# untitled.net
KiCad netlist of a schematic drawn in EAGLE
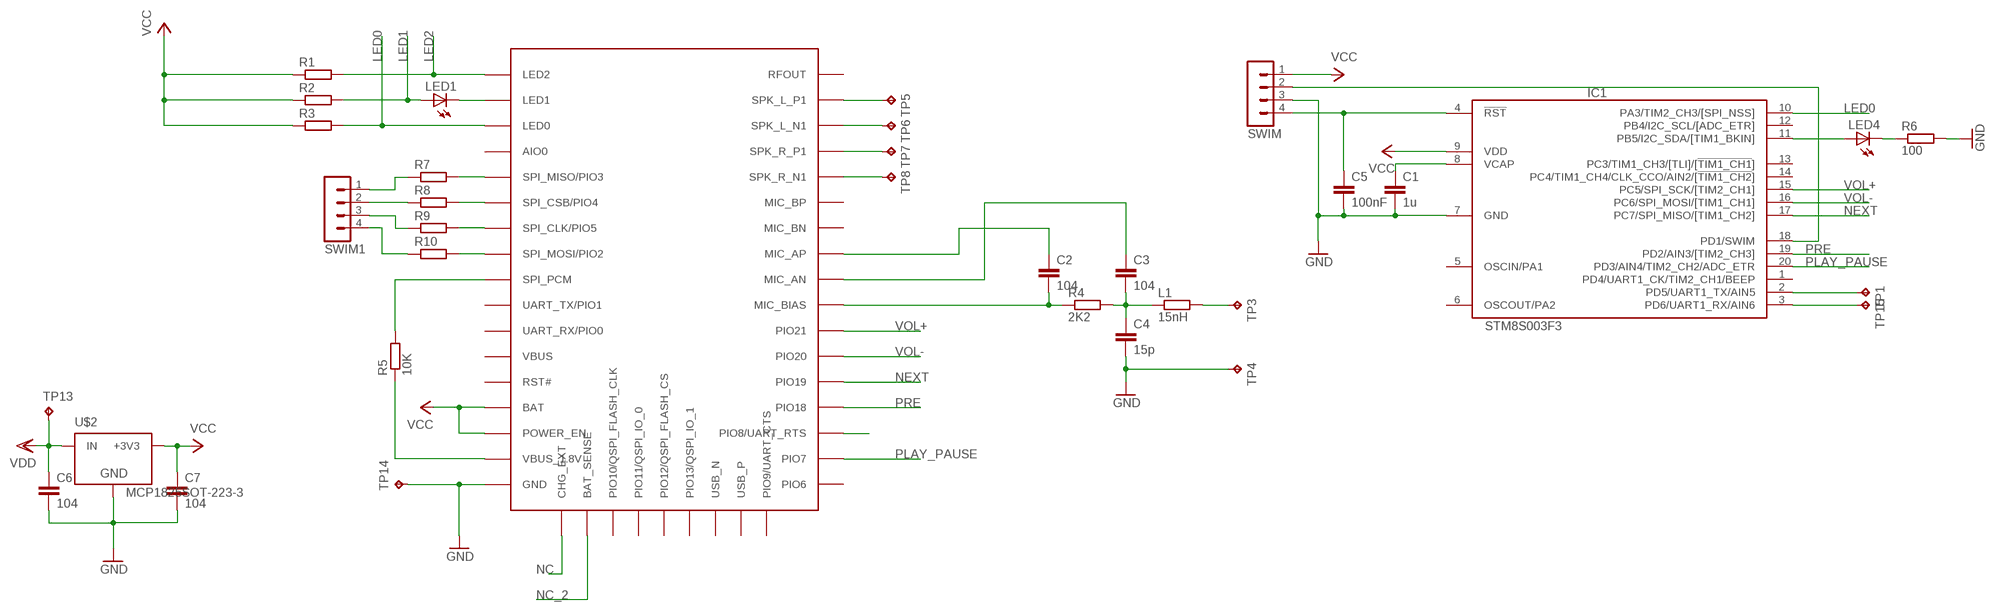
[diagram p0: schematic, sheet 1]

(export (version "E")
  (design (tool "Eeschema 10.0.6"))
  (components
    (comp (ref "C1")
      (value "1u")
      (footprint "eagle-import:C0805")
      (libsource (lib "eagle-import") (part "C-EUC0805"))
    )
    (comp (ref "C2")
      (value "104")
      (footprint "eagle-import:C0805")
      (libsource (lib "eagle-import") (part "C-EUC0805"))
    )
    (comp (ref "C3")
      (value "104")
      (footprint "eagle-import:C0805")
      (libsource (lib "eagle-import") (part "C-EUC0805"))
    )
    (comp (ref "C4")
      (value "15p")
      (footprint "eagle-import:C0805")
      (libsource (lib "eagle-import") (part "C-EUC0805"))
    )
    (comp (ref "C5")
      (value "100nF")
      (footprint "eagle-import:C0805")
      (libsource (lib "eagle-import") (part "C-EUC0805"))
    )
    (comp (ref "C6")
      (value "104")
      (footprint "eagle-import:C0805")
      (libsource (lib "eagle-import") (part "C-EUC0805"))
    )
    (comp (ref "C7")
      (value "104")
      (footprint "eagle-import:C0805")
      (libsource (lib "eagle-import") (part "C-EUC0805"))
    )
    (comp (ref "IC1")
      (value "STM8S003F3")
      (footprint "eagle-import:TSSOP20")
      (libsource (lib "eagle-import") (part "STM8S003F3"))
    )
    (comp (ref "L1")
      (value "15nH")
      (footprint "eagle-import:R0603")
      (libsource (lib "eagle-import") (part "R-EU_R0603"))
    )
    (comp (ref "LED1")
      (value "LEDCHIPLED_0603")
      (footprint "eagle-import:CHIPLED_0603")
      (libsource (lib "eagle-import") (part "LEDCHIPLED_0603"))
    )
    (comp (ref "LED4")
      (value "LEDCHIPLED_0603")
      (footprint "eagle-import:CHIPLED_0603")
      (libsource (lib "eagle-import") (part "LEDCHIPLED_0603"))
    )
    (comp (ref "R1")
      (value "R-EU_R0805")
      (footprint "eagle-import:R0805")
      (libsource (lib "eagle-import") (part "R-EU_R0805"))
    )
    (comp (ref "R2")
      (value "R-EU_R0805")
      (footprint "eagle-import:R0805")
      (libsource (lib "eagle-import") (part "R-EU_R0805"))
    )
    (comp (ref "R3")
      (value "R-EU_R0805")
      (footprint "eagle-import:R0805")
      (libsource (lib "eagle-import") (part "R-EU_R0805"))
    )
    (comp (ref "R4")
      (value "2K2")
      (footprint "eagle-import:R0805")
      (libsource (lib "eagle-import") (part "R-EU_R0805"))
    )
    (comp (ref "R5")
      (value "10K")
      (footprint "eagle-import:R0805")
      (libsource (lib "eagle-import") (part "R-EU_R0805"))
    )
    (comp (ref "R6")
      (value "100")
      (footprint "eagle-import:R0805")
      (libsource (lib "eagle-import") (part "R-EU_R0805"))
    )
    (comp (ref "R7")
      (value "R-EU_R0805")
      (footprint "eagle-import:R0805")
      (libsource (lib "eagle-import") (part "R-EU_R0805"))
    )
    (comp (ref "R8")
      (value "R-EU_R0805")
      (footprint "eagle-import:R0805")
      (libsource (lib "eagle-import") (part "R-EU_R0805"))
    )
    (comp (ref "R9")
      (value "R-EU_R0805")
      (footprint "eagle-import:R0805")
      (libsource (lib "eagle-import") (part "R-EU_R0805"))
    )
    (comp (ref "R10")
      (value "R-EU_R0805")
      (footprint "eagle-import:R0805")
      (libsource (lib "eagle-import") (part "R-EU_R0805"))
    )
    (comp (ref "SWIM")
      (value "MA04-1")
      (footprint "eagle-import:MA04-1")
      (libsource (lib "eagle-import") (part "MA04-1"))
    )
    (comp (ref "SWIM1")
      (value "MA04-1")
      (footprint "eagle-import:MA04-1")
      (libsource (lib "eagle-import") (part "MA04-1"))
    )
    (comp (ref "TP1")
      (value "TPB2,54")
      (footprint "eagle-import:B2,54")
      (libsource (lib "eagle-import") (part "TPB2,54"))
    )
    (comp (ref "TP3")
      (value "TPB2,54")
      (footprint "eagle-import:B2,54")
      (libsource (lib "eagle-import") (part "TPB2,54"))
    )
    (comp (ref "TP4")
      (value "TPB2,54")
      (footprint "eagle-import:B2,54")
      (libsource (lib "eagle-import") (part "TPB2,54"))
    )
    (comp (ref "TP5")
      (value "TPB2,54")
      (footprint "eagle-import:B2,54")
      (libsource (lib "eagle-import") (part "TPB2,54"))
    )
    (comp (ref "TP6")
      (value "TPB2,54")
      (footprint "eagle-import:B2,54")
      (libsource (lib "eagle-import") (part "TPB2,54"))
    )
    (comp (ref "TP7")
      (value "TPB2,54")
      (footprint "eagle-import:B2,54")
      (libsource (lib "eagle-import") (part "TPB2,54"))
    )
    (comp (ref "TP8")
      (value "TPB2,54")
      (footprint "eagle-import:B2,54")
      (libsource (lib "eagle-import") (part "TPB2,54"))
    )
    (comp (ref "TP13")
      (value "TPB2,54")
      (footprint "eagle-import:B2,54")
      (libsource (lib "eagle-import") (part "TPB2,54"))
    )
    (comp (ref "TP14")
      (value "TPB2,54")
      (footprint "eagle-import:B2,54")
      (libsource (lib "eagle-import") (part "TPB2,54"))
    )
    (comp (ref "TP15")
      (value "TPB2,54")
      (footprint "eagle-import:B2,54")
      (libsource (lib "eagle-import") (part "TPB2,54"))
    )
    (comp (ref "U$1")
      (value "F3188")
      (footprint "eagle-import:F3188")
      (libsource (lib "eagle-import") (part "F3188"))
    )
    (comp (ref "U$2")
      (value "MCP1825SOT-223-3")
      (footprint "eagle-import:SOT-223")
      (libsource (lib "eagle-import") (part "MCP1825SOT-223-3"))
    )
  )
  (nets
    (net (code "1") (name "/LED0") (class "Default")
      (node (ref "IC1") (pin "10") (pinfunction "PA3/TIM2_CH3/[SPI_NSS]_10") (pintype "bidirectional"))
      (node (ref "R3") (pin "2") (pinfunction "2_2") (pintype "passive"))
      (node (ref "U$1") (pin "P$3") (pinfunction "LED0_P$3") (pintype "bidirectional"))
    )
    (net (code "2") (name "/LED1") (class "Default")
      (node (ref "LED1") (pin "A") (pinfunction "A_A") (pintype "passive"))
      (node (ref "R2") (pin "2") (pinfunction "2_2") (pintype "passive"))
    )
    (net (code "3") (name "/LED2") (class "Default")
      (node (ref "R1") (pin "2") (pinfunction "2_2") (pintype "passive"))
      (node (ref "U$1") (pin "P$1") (pinfunction "LED2_P$1") (pintype "bidirectional"))
    )
    (net (code "4") (name "/NC") (class "Default")
      (node (ref "U$1") (pin "P$18") (pinfunction "CHG_EXT_P$18") (pintype "bidirectional"))
    )
    (net (code "5") (name "/NC_2") (class "Default")
      (node (ref "U$1") (pin "P$19") (pinfunction "BAT_SENSE_P$19") (pintype "bidirectional"))
    )
    (net (code "6") (name "/NEXT") (class "Default")
      (node (ref "IC1") (pin "17") (pinfunction "PC7/SPI_MISO/[TIM1_CH2]_17") (pintype "bidirectional"))
      (node (ref "U$1") (pin "P$31") (pinfunction "PIO19_P$31") (pintype "bidirectional"))
    )
    (net (code "7") (name "/PLAY_PAUSE") (class "Default")
      (node (ref "IC1") (pin "20") (pinfunction "PD3/AIN4/TIM2_CH2/ADC_ETR_20") (pintype "bidirectional"))
      (node (ref "U$1") (pin "P$28") (pinfunction "PIO7_P$28") (pintype "bidirectional"))
    )
    (net (code "8") (name "/PRE") (class "Default")
      (node (ref "IC1") (pin "19") (pinfunction "PD2/AIN3/[TIM2_CH3]_19") (pintype "bidirectional"))
      (node (ref "U$1") (pin "P$30") (pinfunction "PIO18_P$30") (pintype "bidirectional"))
    )
    (net (code "9") (name "/VBUS") (class "Default")
      (node (ref "U$1") (pin "P$12") (pinfunction "VBUS_P$12") (pintype "power_in"))
    )
    (net (code "10") (name "/VOL+") (class "Default")
      (node (ref "IC1") (pin "15") (pinfunction "PC5/SPI_SCK/[TIM2_CH1]_15") (pintype "bidirectional"))
      (node (ref "U$1") (pin "P$33") (pinfunction "PIO21_P$33") (pintype "bidirectional"))
    )
    (net (code "11") (name "/VOL-") (class "Default")
      (node (ref "IC1") (pin "16") (pinfunction "PC6/SPI_MOSI/[TIM1_CH1]_16") (pintype "bidirectional"))
      (node (ref "U$1") (pin "P$32") (pinfunction "PIO20_P$32") (pintype "bidirectional"))
    )
    (net (code "12") (name "GND") (class "Default")
      (node (ref "C1") (pin "2") (pinfunction "2_2") (pintype "passive"))
      (node (ref "C4") (pin "2") (pinfunction "2_2") (pintype "passive"))
      (node (ref "C5") (pin "2") (pinfunction "2_2") (pintype "passive"))
      (node (ref "C6") (pin "2") (pinfunction "2_2") (pintype "passive"))
      (node (ref "C7") (pin "2") (pinfunction "2_2") (pintype "passive"))
      (node (ref "IC1") (pin "7") (pinfunction "GND_7") (pintype "power_in"))
      (node (ref "R6") (pin "2") (pinfunction "2_2") (pintype "passive"))
      (node (ref "SWIM") (pin "3") (pinfunction "3_3") (pintype "passive"))
      (node (ref "TP14") (pin "TP") (pinfunction "TP_TP") (pintype "input"))
      (node (ref "TP4") (pin "TP") (pinfunction "TP_TP") (pintype "input"))
      (node (ref "U$1") (pin "P$17") (pinfunction "GND_P$17") (pintype "power_in"))
      (node (ref "U$2") (pin "2") (pinfunction "GND_2") (pintype "power_in"))
    )
    (net (code "13") (name "Net-(C3-Pad2)") (class "Default")
      (node (ref "C3") (pin "2") (pinfunction "2_2") (pintype "passive"))
      (node (ref "C4") (pin "1") (pinfunction "1_1") (pintype "passive"))
      (node (ref "L1") (pin "1") (pinfunction "1_1") (pintype "passive"))
      (node (ref "R4") (pin "2") (pinfunction "2_2") (pintype "passive"))
    )
    (net (code "14") (name "Net-(IC1-PB5{slash}I2C_SDA{slash}[TIM1_BKIN])") (class "Default")
      (node (ref "IC1") (pin "11") (pinfunction "PB5/I2C_SDA/[TIM1_BKIN]_11") (pintype "bidirectional"))
      (node (ref "LED4") (pin "A") (pinfunction "A_A") (pintype "passive"))
    )
    (net (code "15") (name "Net-(IC1-PD1{slash}SWIM)") (class "Default")
      (node (ref "IC1") (pin "18") (pinfunction "PD1/SWIM_18") (pintype "bidirectional"))
      (node (ref "SWIM") (pin "2") (pinfunction "2_2") (pintype "passive"))
    )
    (net (code "16") (name "Net-(IC1-PD5{slash}UART1_TX{slash}AIN5)") (class "Default")
      (node (ref "IC1") (pin "2") (pinfunction "PD5/UART1_TX/AIN5_2") (pintype "bidirectional"))
      (node (ref "TP1") (pin "TP") (pinfunction "TP_TP") (pintype "input"))
    )
    (net (code "17") (name "Net-(IC1-PD6{slash}UART1_RX{slash}AIN6)") (class "Default")
      (node (ref "IC1") (pin "3") (pinfunction "PD6/UART1_RX/AIN6_3") (pintype "bidirectional"))
      (node (ref "TP15") (pin "TP") (pinfunction "TP_TP") (pintype "input"))
    )
    (net (code "18") (name "Net-(IC1-VCAP)") (class "Default")
      (node (ref "C1") (pin "1") (pinfunction "1_1") (pintype "passive"))
      (node (ref "IC1") (pin "8") (pinfunction "VCAP_8") (pintype "power_in"))
    )
    (net (code "19") (name "Net-(IC1-~{RST})") (class "Default")
      (node (ref "C5") (pin "1") (pinfunction "1_1") (pintype "passive"))
      (node (ref "IC1") (pin "4") (pinfunction "~{RST}_4") (pintype "input"))
      (node (ref "SWIM") (pin "4") (pinfunction "4_4") (pintype "passive"))
    )
    (net (code "20") (name "Net-(L1-Pad2)") (class "Default")
      (node (ref "L1") (pin "2") (pinfunction "2_2") (pintype "passive"))
      (node (ref "TP3") (pin "TP") (pinfunction "TP_TP") (pintype "input"))
    )
    (net (code "21") (name "Net-(LED4-PadC)") (class "Default")
      (node (ref "LED4") (pin "C") (pinfunction "C_C") (pintype "passive"))
      (node (ref "R6") (pin "1") (pinfunction "1_1") (pintype "passive"))
    )
    (net (code "22") (name "Net-(R7-Pad1)") (class "Default")
      (node (ref "R7") (pin "1") (pinfunction "1_1") (pintype "passive"))
      (node (ref "SWIM1") (pin "1") (pinfunction "1_1") (pintype "passive"))
    )
    (net (code "23") (name "Net-(R8-Pad1)") (class "Default")
      (node (ref "R8") (pin "1") (pinfunction "1_1") (pintype "passive"))
      (node (ref "SWIM1") (pin "2") (pinfunction "2_2") (pintype "passive"))
    )
    (net (code "24") (name "Net-(R9-Pad1)") (class "Default")
      (node (ref "R9") (pin "1") (pinfunction "1_1") (pintype "passive"))
      (node (ref "SWIM1") (pin "3") (pinfunction "3_3") (pintype "passive"))
    )
    (net (code "25") (name "Net-(R10-Pad1)") (class "Default")
      (node (ref "R10") (pin "1") (pinfunction "1_1") (pintype "passive"))
      (node (ref "SWIM1") (pin "4") (pinfunction "4_4") (pintype "passive"))
    )
    (net (code "26") (name "Net-(U$1-LED1)") (class "Default")
      (node (ref "LED1") (pin "C") (pinfunction "C_C") (pintype "passive"))
      (node (ref "U$1") (pin "P$2") (pinfunction "LED1_P$2") (pintype "bidirectional"))
    )
    (net (code "27") (name "Net-(U$1-MIC_AN)") (class "Default")
      (node (ref "C3") (pin "1") (pinfunction "1_1") (pintype "passive"))
      (node (ref "U$1") (pin "P$35") (pinfunction "MIC_AN_P$35") (pintype "bidirectional"))
    )
    (net (code "28") (name "Net-(U$1-MIC_AP)") (class "Default")
      (node (ref "C2") (pin "1") (pinfunction "1_1") (pintype "passive"))
      (node (ref "U$1") (pin "P$36") (pinfunction "MIC_AP_P$36") (pintype "bidirectional"))
    )
    (net (code "29") (name "Net-(U$1-MIC_BIAS)") (class "Default")
      (node (ref "C2") (pin "2") (pinfunction "2_2") (pintype "passive"))
      (node (ref "R4") (pin "1") (pinfunction "1_1") (pintype "passive"))
      (node (ref "U$1") (pin "P$34") (pinfunction "MIC_BIAS_P$34") (pintype "bidirectional"))
    )
    (net (code "30") (name "Net-(U$1-SPI_CLK{slash}PIO5)") (class "Default")
      (node (ref "R9") (pin "2") (pinfunction "2_2") (pintype "passive"))
      (node (ref "U$1") (pin "P$7") (pinfunction "SPI_CLK/PIO5_P$7") (pintype "bidirectional"))
    )
    (net (code "31") (name "Net-(U$1-SPI_CSB{slash}PIO4)") (class "Default")
      (node (ref "R8") (pin "2") (pinfunction "2_2") (pintype "passive"))
      (node (ref "U$1") (pin "P$6") (pinfunction "SPI_CSB/PIO4_P$6") (pintype "bidirectional"))
    )
    (net (code "32") (name "Net-(U$1-SPI_MISO{slash}PIO3)") (class "Default")
      (node (ref "R7") (pin "2") (pinfunction "2_2") (pintype "passive"))
      (node (ref "U$1") (pin "P$5") (pinfunction "SPI_MISO/PIO3_P$5") (pintype "bidirectional"))
    )
    (net (code "33") (name "Net-(U$1-SPI_MOSI{slash}PIO2)") (class "Default")
      (node (ref "R10") (pin "2") (pinfunction "2_2") (pintype "passive"))
      (node (ref "U$1") (pin "P$8") (pinfunction "SPI_MOSI/PIO2_P$8") (pintype "bidirectional"))
    )
    (net (code "34") (name "Net-(U$1-SPI_PCM)") (class "Default")
      (node (ref "R5") (pin "2") (pinfunction "2_2") (pintype "passive"))
      (node (ref "U$1") (pin "P$9") (pinfunction "SPI_PCM_P$9") (pintype "bidirectional"))
    )
    (net (code "35") (name "Net-(U$1-SPK_L_N1)") (class "Default")
      (node (ref "TP6") (pin "TP") (pinfunction "TP_TP") (pintype "input"))
      (node (ref "U$1") (pin "P$41") (pinfunction "SPK_L_N1_P$41") (pintype "bidirectional"))
    )
    (net (code "36") (name "Net-(U$1-SPK_L_P1)") (class "Default")
      (node (ref "TP5") (pin "TP") (pinfunction "TP_TP") (pintype "input"))
      (node (ref "U$1") (pin "P$42") (pinfunction "SPK_L_P1_P$42") (pintype "bidirectional"))
    )
    (net (code "37") (name "Net-(U$1-SPK_R_N1)") (class "Default")
      (node (ref "TP8") (pin "TP") (pinfunction "TP_TP") (pintype "input"))
      (node (ref "U$1") (pin "P$39") (pinfunction "SPK_R_N1_P$39") (pintype "bidirectional"))
    )
    (net (code "38") (name "Net-(U$1-SPK_R_P1)") (class "Default")
      (node (ref "TP7") (pin "TP") (pinfunction "TP_TP") (pintype "input"))
      (node (ref "U$1") (pin "P$40") (pinfunction "SPK_R_P1_P$40") (pintype "bidirectional"))
    )
    (net (code "39") (name "Net-(U$1-VBUS_1.8V)") (class "Default")
      (node (ref "R5") (pin "1") (pinfunction "1_1") (pintype "passive"))
      (node (ref "U$1") (pin "P$16") (pinfunction "VBUS_1.8V_P$16") (pintype "power_in"))
    )
    (net (code "40") (name "VCC") (class "Default")
      (node (ref "C7") (pin "1") (pinfunction "1_1") (pintype "passive"))
      (node (ref "IC1") (pin "9") (pinfunction "VDD_9") (pintype "power_in"))
      (node (ref "R1") (pin "1") (pinfunction "1_1") (pintype "passive"))
      (node (ref "R2") (pin "1") (pinfunction "1_1") (pintype "passive"))
      (node (ref "R3") (pin "1") (pinfunction "1_1") (pintype "passive"))
      (node (ref "SWIM") (pin "1") (pinfunction "1_1") (pintype "passive"))
      (node (ref "U$1") (pin "P$14") (pinfunction "BAT_P$14") (pintype "power_in"))
      (node (ref "U$1") (pin "P$15") (pinfunction "POWER_EN_P$15") (pintype "bidirectional"))
      (node (ref "U$2") (pin "3") (pinfunction "+3V3_3") (pintype "power_in"))
    )
    (net (code "41") (name "VDD") (class "Default")
      (node (ref "C6") (pin "1") (pinfunction "1_1") (pintype "passive"))
      (node (ref "TP13") (pin "TP") (pinfunction "TP_TP") (pintype "input"))
      (node (ref "U$2") (pin "1") (pinfunction "IN_1") (pintype "power_in"))
    )
    (net (code "42") (name "unconnected-(IC1-OSCIN{slash}PA1-Pad5)") (class "Default")
      (node (ref "IC1") (pin "5") (pinfunction "OSCIN/PA1_5") (pintype "bidirectional"))
    )
    (net (code "43") (name "unconnected-(IC1-OSCOUT{slash}PA2-Pad6)") (class "Default")
      (node (ref "IC1") (pin "6") (pinfunction "OSCOUT/PA2_6") (pintype "bidirectional"))
    )
    (net (code "44") (name "unconnected-(IC1-PB4{slash}I2C_SCL{slash}[ADC_ETR]-Pad12)") (class "Default")
      (node (ref "IC1") (pin "12") (pinfunction "PB4/I2C_SCL/[ADC_ETR]_12") (pintype "bidirectional"))
    )
    (net (code "45") (name "unconnected-(IC1-PC3{slash}TIM1_CH3{slash}[TLI]{slash}[~{TIM1_CH1}]-Pad13)") (class "Default")
      (node (ref "IC1") (pin "13") (pinfunction "PC3/TIM1_CH3/[TLI]/[~{TIM1_CH1}]_13") (pintype "bidirectional"))
    )
    (net (code "46") (name "unconnected-(IC1-PC4{slash}TIM1_CH4{slash}CLK_CCO{slash}AIN2{slash}[~{TIM1_CH2}]-Pad14)") (class "Default")
      (node (ref "IC1") (pin "14") (pinfunction "PC4/TIM1_CH4/CLK_CCO/AIN2/[~{TIM1_CH2}]_14") (pintype "bidirectional"))
    )
    (net (code "47") (name "unconnected-(IC1-PD4{slash}UART1_CK{slash}TIM2_CH1{slash}BEEP-Pad1)") (class "Default")
      (node (ref "IC1") (pin "1") (pinfunction "PD4/UART1_CK/TIM2_CH1/BEEP_1") (pintype "bidirectional"))
    )
    (net (code "48") (name "unconnected-(U$1-AIO0-PadP$4)") (class "Default")
      (node (ref "U$1") (pin "P$4") (pinfunction "AIO0_P$4") (pintype "bidirectional"))
    )
    (net (code "49") (name "unconnected-(U$1-MIC_BN-PadP$37)") (class "Default")
      (node (ref "U$1") (pin "P$37") (pinfunction "MIC_BN_P$37") (pintype "bidirectional"))
    )
    (net (code "50") (name "unconnected-(U$1-MIC_BP-PadP$38)") (class "Default")
      (node (ref "U$1") (pin "P$38") (pinfunction "MIC_BP_P$38") (pintype "bidirectional"))
    )
    (net (code "51") (name "unconnected-(U$1-PIO6-PadP$27)") (class "Default")
      (node (ref "U$1") (pin "P$27") (pinfunction "PIO6_P$27") (pintype "bidirectional"))
    )
    (net (code "52") (name "unconnected-(U$1-PIO8{slash}UART_RTS-PadP$29)") (class "Default")
      (node (ref "U$1") (pin "P$29") (pinfunction "PIO8/UART_RTS_P$29") (pintype "bidirectional"))
    )
    (net (code "53") (name "unconnected-(U$1-PIO9{slash}UART_CTS-PadP$26)") (class "Default")
      (node (ref "U$1") (pin "P$26") (pinfunction "PIO9/UART_CTS_P$26") (pintype "bidirectional"))
    )
    (net (code "54") (name "unconnected-(U$1-PIO10{slash}QSPI_FLASH_CLK-PadP$20)") (class "Default")
      (node (ref "U$1") (pin "P$20") (pinfunction "PIO10/QSPI_FLASH_CLK_P$20") (pintype "bidirectional"))
    )
    (net (code "55") (name "unconnected-(U$1-PIO11{slash}QSPI_IO_0-PadP$21)") (class "Default")
      (node (ref "U$1") (pin "P$21") (pinfunction "PIO11/QSPI_IO_0_P$21") (pintype "bidirectional"))
    )
    (net (code "56") (name "unconnected-(U$1-PIO12{slash}QSPI_FLASH_CS-PadP$22)") (class "Default")
      (node (ref "U$1") (pin "P$22") (pinfunction "PIO12/QSPI_FLASH_CS_P$22") (pintype "bidirectional"))
    )
    (net (code "57") (name "unconnected-(U$1-PIO13{slash}QSPI_IO_1-PadP$23)") (class "Default")
      (node (ref "U$1") (pin "P$23") (pinfunction "PIO13/QSPI_IO_1_P$23") (pintype "bidirectional"))
    )
    (net (code "58") (name "unconnected-(U$1-RFOUT-PadP$43)") (class "Default")
      (node (ref "U$1") (pin "P$43") (pinfunction "RFOUT_P$43") (pintype "bidirectional"))
    )
    (net (code "59") (name "unconnected-(U$1-RST#-PadP$13)") (class "Default")
      (node (ref "U$1") (pin "P$13") (pinfunction "RST#_P$13") (pintype "bidirectional"))
    )
    (net (code "60") (name "unconnected-(U$1-UART_RX{slash}PIO0-PadP$11)") (class "Default")
      (node (ref "U$1") (pin "P$11") (pinfunction "UART_RX/PIO0_P$11") (pintype "bidirectional"))
    )
    (net (code "61") (name "unconnected-(U$1-UART_TX{slash}PIO1-PadP$10)") (class "Default")
      (node (ref "U$1") (pin "P$10") (pinfunction "UART_TX/PIO1_P$10") (pintype "bidirectional"))
    )
    (net (code "62") (name "unconnected-(U$1-USB_N-PadP$24)") (class "Default")
      (node (ref "U$1") (pin "P$24") (pinfunction "USB_N_P$24") (pintype "bidirectional"))
    )
    (net (code "63") (name "unconnected-(U$1-USB_P-PadP$25)") (class "Default")
      (node (ref "U$1") (pin "P$25") (pinfunction "USB_P_P$25") (pintype "bidirectional"))
    )
  )
)
